# M129A.net
KiCad netlist of a schematic drawn in EAGLE
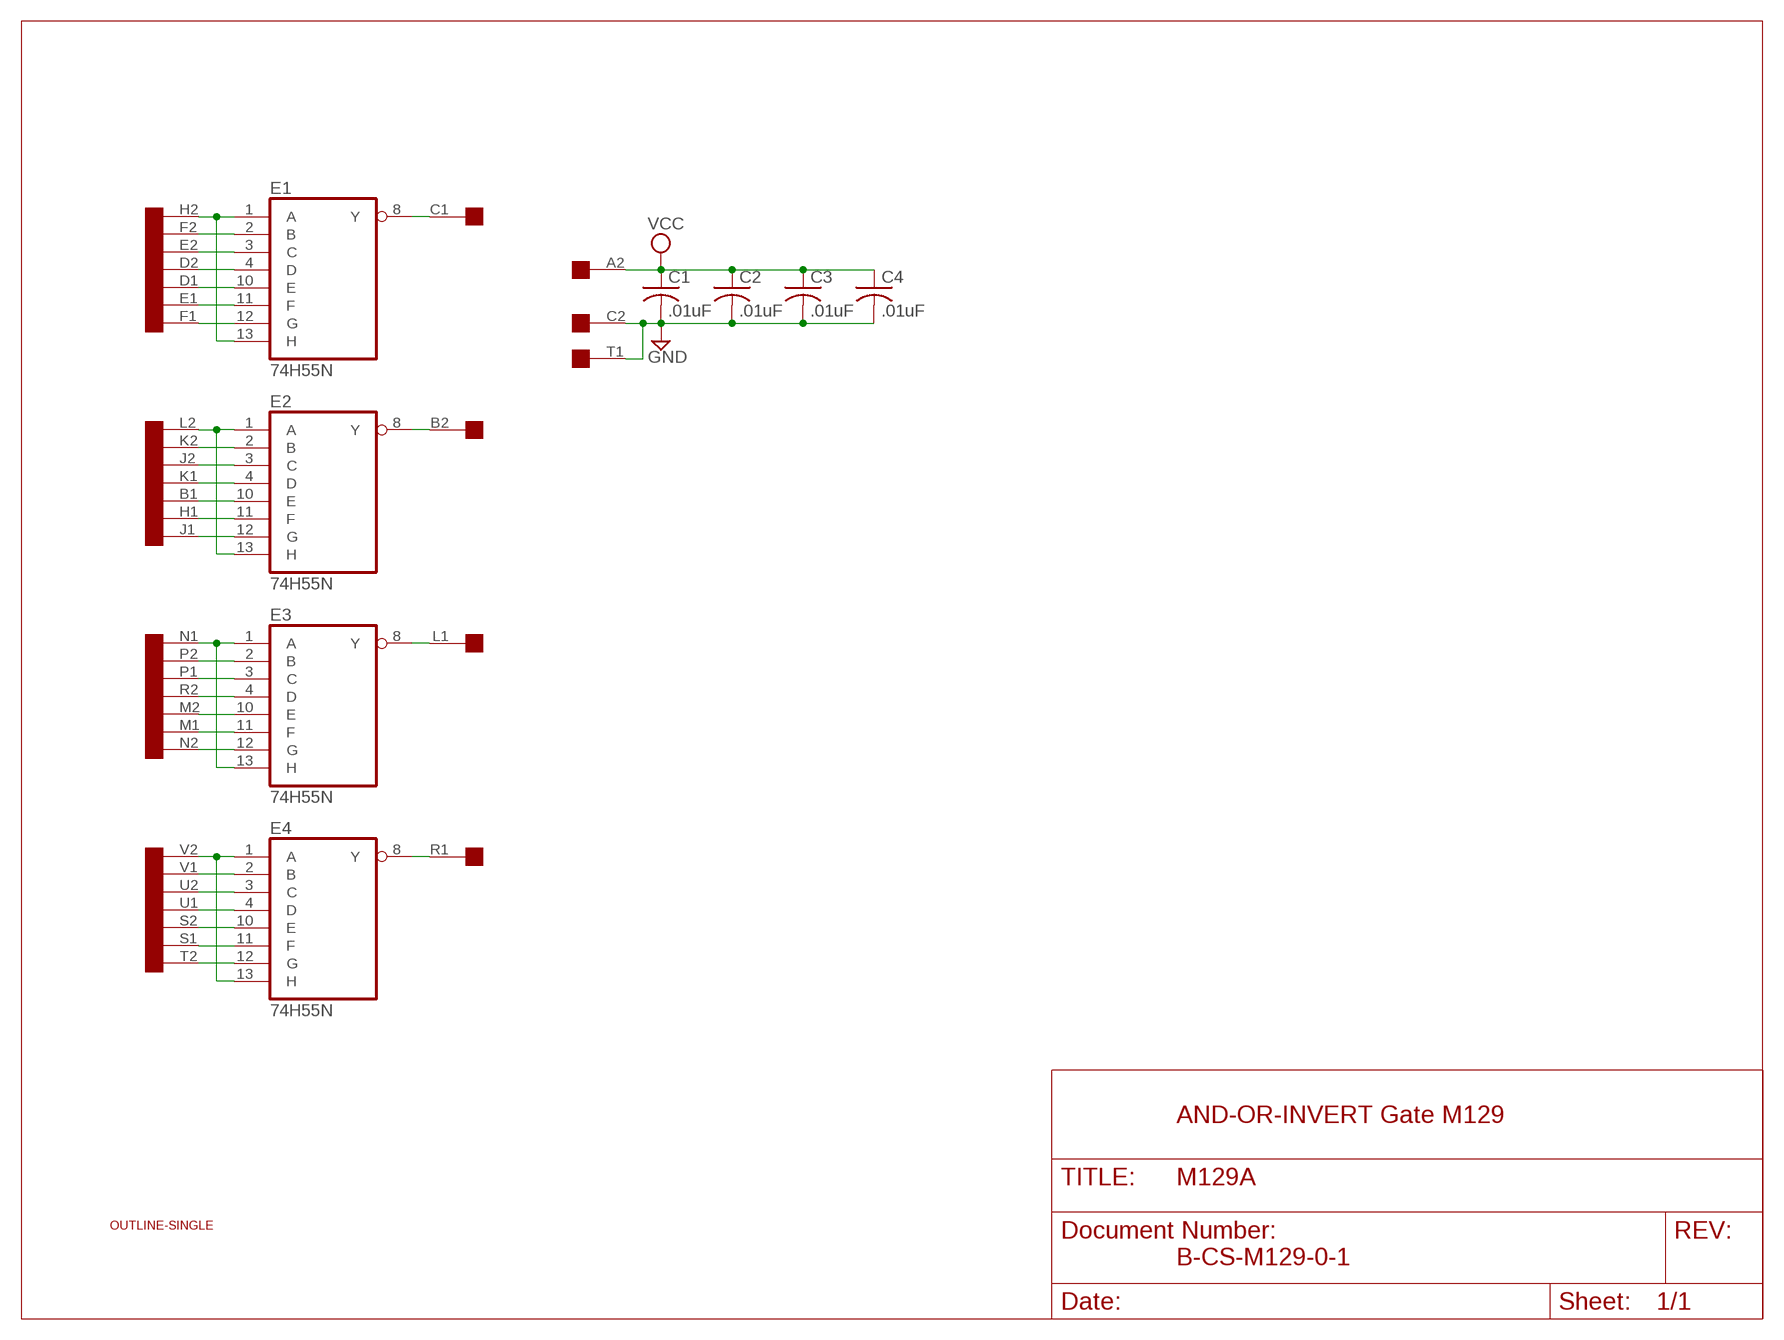
[diagram p0: schematic, sheet 1]

(export (version "E")
  (design (tool "Eeschema 10.0.6"))
  (components
    (comp (ref "C1")
      (value ".01uF")
      (footprint "eagle-import:C050-025X075")
      (libsource (lib "eagle-import") (part "C-US050-025X075"))
    )
    (comp (ref "C2")
      (value ".01uF")
      (footprint "eagle-import:C050-025X075")
      (libsource (lib "eagle-import") (part "C-US050-025X075"))
    )
    (comp (ref "C3")
      (value ".01uF")
      (footprint "eagle-import:C050-025X075")
      (libsource (lib "eagle-import") (part "C-US050-025X075"))
    )
    (comp (ref "C4")
      (value ".01uF")
      (footprint "eagle-import:C050-025X075")
      (libsource (lib "eagle-import") (part "C-US050-025X075"))
    )
    (comp (ref "E1")
      (value "74H55N")
      (footprint "eagle-import:DIL14")
      (libsource (lib "eagle-import") (part "7455NLS"))
    )
    (comp (ref "E2")
      (value "74H55N")
      (footprint "eagle-import:DIL14")
      (libsource (lib "eagle-import") (part "7455NLS"))
    )
    (comp (ref "E3")
      (value "74H55N")
      (footprint "eagle-import:DIL14")
      (libsource (lib "eagle-import") (part "7455NLS"))
    )
    (comp (ref "E4")
      (value "74H55N")
      (footprint "eagle-import:DIL14")
      (libsource (lib "eagle-import") (part "7455NLS"))
    )
    (comp (ref "U$1")
      (value "SINGLE")
      (footprint "eagle-import:EDGE-CON2")
      (libsource (lib "eagle-import") (part "SINGLE"))
    )
    (comp (ref "U$2")
      (value "OUTLINE-SINGLE")
      (footprint "eagle-import:SINGLE")
      (libsource (lib "eagle-import") (part "OUTLINE-SINGLE"))
    )
  )
  (nets
    (net (code "1") (name "GND") (class "Default")
      (node (ref "C1") (pin "2") (pinfunction "2_2") (pintype "passive"))
      (node (ref "C2") (pin "2") (pinfunction "2_2") (pintype "passive"))
      (node (ref "C3") (pin "2") (pinfunction "2_2") (pintype "passive"))
      (node (ref "C4") (pin "2") (pinfunction "2_2") (pintype "passive"))
      (node (ref "U$1") (pin "C2") (pinfunction "1_C2") (pintype "bidirectional"))
      (node (ref "U$1") (pin "T1") (pinfunction "1_T1") (pintype "bidirectional"))
    )
    (net (code "2") (name "Net-(E1A-A)") (class "Default")
      (node (ref "E1") (pin "1") (pinfunction "A_1") (pintype "input"))
      (node (ref "E1") (pin "13") (pinfunction "H_13") (pintype "input"))
      (node (ref "U$1") (pin "H2") (pinfunction "1_H2") (pintype "bidirectional"))
    )
    (net (code "3") (name "Net-(E1A-B)") (class "Default")
      (node (ref "E1") (pin "2") (pinfunction "B_2") (pintype "input"))
      (node (ref "U$1") (pin "F2") (pinfunction "1_F2") (pintype "bidirectional"))
    )
    (net (code "4") (name "Net-(E1A-C)") (class "Default")
      (node (ref "E1") (pin "3") (pinfunction "C_3") (pintype "input"))
      (node (ref "U$1") (pin "E2") (pinfunction "1_E2") (pintype "bidirectional"))
    )
    (net (code "5") (name "Net-(E1A-D)") (class "Default")
      (node (ref "E1") (pin "4") (pinfunction "D_4") (pintype "input"))
      (node (ref "U$1") (pin "D2") (pinfunction "1_D2") (pintype "bidirectional"))
    )
    (net (code "6") (name "Net-(E1A-E)") (class "Default")
      (node (ref "E1") (pin "10") (pinfunction "E_10") (pintype "input"))
      (node (ref "U$1") (pin "D1") (pinfunction "1_D1") (pintype "bidirectional"))
    )
    (net (code "7") (name "Net-(E1A-F)") (class "Default")
      (node (ref "E1") (pin "11") (pinfunction "F_11") (pintype "input"))
      (node (ref "U$1") (pin "E1") (pinfunction "1_E1") (pintype "bidirectional"))
    )
    (net (code "8") (name "Net-(E1A-G)") (class "Default")
      (node (ref "E1") (pin "12") (pinfunction "G_12") (pintype "input"))
      (node (ref "U$1") (pin "F1") (pinfunction "1_F1") (pintype "bidirectional"))
    )
    (net (code "9") (name "Net-(E1A-Y)") (class "Default")
      (node (ref "E1") (pin "8") (pinfunction "Y_8") (pintype "output"))
      (node (ref "U$1") (pin "C1") (pinfunction "1_C1") (pintype "bidirectional"))
    )
    (net (code "10") (name "Net-(E2A-A)") (class "Default")
      (node (ref "E2") (pin "1") (pinfunction "A_1") (pintype "input"))
      (node (ref "E2") (pin "13") (pinfunction "H_13") (pintype "input"))
      (node (ref "U$1") (pin "L2") (pinfunction "1_L2") (pintype "bidirectional"))
    )
    (net (code "11") (name "Net-(E2A-B)") (class "Default")
      (node (ref "E2") (pin "2") (pinfunction "B_2") (pintype "input"))
      (node (ref "U$1") (pin "K2") (pinfunction "1_K2") (pintype "bidirectional"))
    )
    (net (code "12") (name "Net-(E2A-C)") (class "Default")
      (node (ref "E2") (pin "3") (pinfunction "C_3") (pintype "input"))
      (node (ref "U$1") (pin "J2") (pinfunction "1_J2") (pintype "bidirectional"))
    )
    (net (code "13") (name "Net-(E2A-D)") (class "Default")
      (node (ref "E2") (pin "4") (pinfunction "D_4") (pintype "input"))
      (node (ref "U$1") (pin "K1") (pinfunction "1_K1") (pintype "bidirectional"))
    )
    (net (code "14") (name "Net-(E2A-E)") (class "Default")
      (node (ref "E2") (pin "10") (pinfunction "E_10") (pintype "input"))
      (node (ref "U$1") (pin "B1") (pinfunction "1_B1") (pintype "bidirectional"))
    )
    (net (code "15") (name "Net-(E2A-F)") (class "Default")
      (node (ref "E2") (pin "11") (pinfunction "F_11") (pintype "input"))
      (node (ref "U$1") (pin "H1") (pinfunction "1_H1") (pintype "bidirectional"))
    )
    (net (code "16") (name "Net-(E2A-G)") (class "Default")
      (node (ref "E2") (pin "12") (pinfunction "G_12") (pintype "input"))
      (node (ref "U$1") (pin "J1") (pinfunction "1_J1") (pintype "bidirectional"))
    )
    (net (code "17") (name "Net-(E2A-Y)") (class "Default")
      (node (ref "E2") (pin "8") (pinfunction "Y_8") (pintype "output"))
      (node (ref "U$1") (pin "B2") (pinfunction "1_B2") (pintype "bidirectional"))
    )
    (net (code "18") (name "Net-(E3A-A)") (class "Default")
      (node (ref "E3") (pin "1") (pinfunction "A_1") (pintype "input"))
      (node (ref "E3") (pin "13") (pinfunction "H_13") (pintype "input"))
      (node (ref "U$1") (pin "N1") (pinfunction "1_N1") (pintype "bidirectional"))
    )
    (net (code "19") (name "Net-(E3A-B)") (class "Default")
      (node (ref "E3") (pin "2") (pinfunction "B_2") (pintype "input"))
      (node (ref "U$1") (pin "P2") (pinfunction "1_P2") (pintype "bidirectional"))
    )
    (net (code "20") (name "Net-(E3A-C)") (class "Default")
      (node (ref "E3") (pin "3") (pinfunction "C_3") (pintype "input"))
      (node (ref "U$1") (pin "P1") (pinfunction "1_P1") (pintype "bidirectional"))
    )
    (net (code "21") (name "Net-(E3A-D)") (class "Default")
      (node (ref "E3") (pin "4") (pinfunction "D_4") (pintype "input"))
      (node (ref "U$1") (pin "R2") (pinfunction "1_R2") (pintype "bidirectional"))
    )
    (net (code "22") (name "Net-(E3A-E)") (class "Default")
      (node (ref "E3") (pin "10") (pinfunction "E_10") (pintype "input"))
      (node (ref "U$1") (pin "M2") (pinfunction "1_M2") (pintype "bidirectional"))
    )
    (net (code "23") (name "Net-(E3A-F)") (class "Default")
      (node (ref "E3") (pin "11") (pinfunction "F_11") (pintype "input"))
      (node (ref "U$1") (pin "M1") (pinfunction "1_M1") (pintype "bidirectional"))
    )
    (net (code "24") (name "Net-(E3A-G)") (class "Default")
      (node (ref "E3") (pin "12") (pinfunction "G_12") (pintype "input"))
      (node (ref "U$1") (pin "N2") (pinfunction "1_N2") (pintype "bidirectional"))
    )
    (net (code "25") (name "Net-(E3A-Y)") (class "Default")
      (node (ref "E3") (pin "8") (pinfunction "Y_8") (pintype "output"))
      (node (ref "U$1") (pin "L1") (pinfunction "1_L1") (pintype "bidirectional"))
    )
    (net (code "26") (name "Net-(E4A-A)") (class "Default")
      (node (ref "E4") (pin "1") (pinfunction "A_1") (pintype "input"))
      (node (ref "E4") (pin "13") (pinfunction "H_13") (pintype "input"))
      (node (ref "U$1") (pin "V2") (pinfunction "1_V2") (pintype "bidirectional"))
    )
    (net (code "27") (name "Net-(E4A-B)") (class "Default")
      (node (ref "E4") (pin "2") (pinfunction "B_2") (pintype "input"))
      (node (ref "U$1") (pin "V1") (pinfunction "1_V1") (pintype "bidirectional"))
    )
    (net (code "28") (name "Net-(E4A-C)") (class "Default")
      (node (ref "E4") (pin "3") (pinfunction "C_3") (pintype "input"))
      (node (ref "U$1") (pin "U2") (pinfunction "1_U2") (pintype "bidirectional"))
    )
    (net (code "29") (name "Net-(E4A-D)") (class "Default")
      (node (ref "E4") (pin "4") (pinfunction "D_4") (pintype "input"))
      (node (ref "U$1") (pin "U1") (pinfunction "1_U1") (pintype "bidirectional"))
    )
    (net (code "30") (name "Net-(E4A-E)") (class "Default")
      (node (ref "E4") (pin "10") (pinfunction "E_10") (pintype "input"))
      (node (ref "U$1") (pin "S2") (pinfunction "1_S2") (pintype "bidirectional"))
    )
    (net (code "31") (name "Net-(E4A-F)") (class "Default")
      (node (ref "E4") (pin "11") (pinfunction "F_11") (pintype "input"))
      (node (ref "U$1") (pin "S1") (pinfunction "1_S1") (pintype "bidirectional"))
    )
    (net (code "32") (name "Net-(E4A-G)") (class "Default")
      (node (ref "E4") (pin "12") (pinfunction "G_12") (pintype "input"))
      (node (ref "U$1") (pin "T2") (pinfunction "1_T2") (pintype "bidirectional"))
    )
    (net (code "33") (name "Net-(E4A-Y)") (class "Default")
      (node (ref "E4") (pin "8") (pinfunction "Y_8") (pintype "output"))
      (node (ref "U$1") (pin "R1") (pinfunction "1_R1") (pintype "bidirectional"))
    )
    (net (code "34") (name "VCC") (class "Default")
      (node (ref "C1") (pin "1") (pinfunction "1_1") (pintype "passive"))
      (node (ref "C2") (pin "1") (pinfunction "1_1") (pintype "passive"))
      (node (ref "C3") (pin "1") (pinfunction "1_1") (pintype "passive"))
      (node (ref "C4") (pin "1") (pinfunction "1_1") (pintype "passive"))
      (node (ref "U$1") (pin "A2") (pinfunction "1_A2") (pintype "bidirectional"))
    )
  )
)
